# Alternative_bloinking_circuit_v0.net
KiCad netlist of a schematic drawn in EAGLE
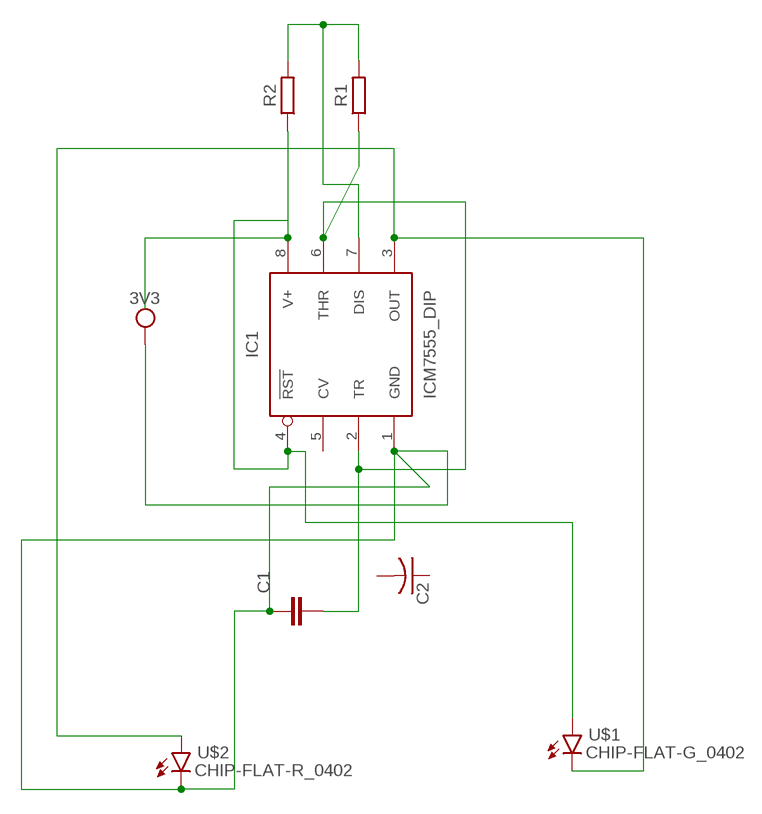
[diagram p0: schematic, sheet 1]

(export (version "E")
  (design (tool "Eeschema 10.0.6"))
  (components
    (comp (ref "C1")
      (value "C_CHIP-0402(1005-METRIC)")
      (footprint "eagle-import:CAPC1005X60")
      (libsource (lib "eagle-import") (part "CCHIP-0402(1005-METRIC)_"))
    )
    (comp (ref "C2")
      (value "C-US_CHIP-0402(1005-METRIC)")
      (footprint "eagle-import:CAPC1005X60")
      (libsource (lib "eagle-import") (part "C-USCHIP-0402(1005-METRIC)_"))
    )
    (comp (ref "IC1")
      (value "ICM7555_DIP")
      (footprint "eagle-import:DIP826W53P254L959H508Q8B")
      (fields
        (field (name "MANUFACTURER") "Renesas Electronics America Inc ")
        (field (name "MPN") "ICM7555IPAZ ")
      )
      (libsource (lib "eagle-import") (part "555_DIPICM7"))
    )
    (comp (ref "R1")
      (value "R_AXIAL-11.7MM-PITCH")
      (footprint "eagle-import:RESAD1176W63L850D250B")
      (libsource (lib "eagle-import") (part "RAXIAL-11.7MM-PITCH_"))
    )
    (comp (ref "R2")
      (value "R_AXIAL-7.2MM-PITCH")
      (footprint "eagle-import:RESAD724W46L381D178B")
      (libsource (lib "eagle-import") (part "RAXIAL-7.2MM-PITCH_"))
    )
    (comp (ref "U$1")
      (value "CHIP-FLAT-G_0402")
      (footprint "eagle-import:LEDC1005X25N")
      (libsource (lib "eagle-import") (part "CHIP-FLAT-G_0402"))
    )
    (comp (ref "U$2")
      (value "CHIP-FLAT-R_0402")
      (footprint "eagle-import:LEDC1005X25N")
      (libsource (lib "eagle-import") (part "CHIP-FLAT-R_0402"))
    )
  )
  (nets
    (net (code "1") (name "3V3") (class "Default")
      (node (ref "C1") (pin "1") (pinfunction "1_1") (pintype "passive"))
      (node (ref "IC1") (pin "1") (pinfunction "GND_1") (pintype "power_in"))
      (node (ref "U$2") (pin "C") (pinfunction "C_C") (pintype "passive"))
    )
    (net (code "2") (name "Net-(IC1-DIS)") (class "Default")
      (node (ref "IC1") (pin "7") (pinfunction "DIS_7") (pintype "input"))
      (node (ref "R1") (pin "2") (pinfunction "2_2") (pintype "passive"))
      (node (ref "R2") (pin "2") (pinfunction "2_2") (pintype "passive"))
    )
    (net (code "3") (name "Net-(IC1-OUT)") (class "Default")
      (node (ref "IC1") (pin "3") (pinfunction "OUT_3") (pintype "output"))
      (node (ref "U$1") (pin "C") (pinfunction "C_C") (pintype "passive"))
      (node (ref "U$2") (pin "A") (pinfunction "A_A") (pintype "passive"))
    )
    (net (code "4") (name "Net-(IC1-THR)") (class "Default")
      (node (ref "C1") (pin "2") (pinfunction "2_2") (pintype "passive"))
      (node (ref "IC1") (pin "2") (pinfunction "TR_2") (pintype "input"))
      (node (ref "IC1") (pin "6") (pinfunction "THR_6") (pintype "input"))
      (node (ref "R1") (pin "1") (pinfunction "1_1") (pintype "passive"))
    )
    (net (code "5") (name "Net-(IC1-V+)") (class "Default")
      (node (ref "IC1") (pin "4") (pinfunction "~{RST}_4") (pintype "input"))
      (node (ref "IC1") (pin "8") (pinfunction "V+_8") (pintype "power_in"))
      (node (ref "R2") (pin "1") (pinfunction "1_1") (pintype "passive"))
      (node (ref "U$1") (pin "A") (pinfunction "A_A") (pintype "passive"))
    )
    (net (code "6") (name "unconnected-(C2-Pad1)") (class "Default")
      (node (ref "C2") (pin "1") (pinfunction "1_1") (pintype "passive"))
    )
    (net (code "7") (name "unconnected-(C2-Pad2)") (class "Default")
      (node (ref "C2") (pin "2") (pinfunction "2_2") (pintype "passive"))
    )
    (net (code "8") (name "unconnected-(IC1-CV-Pad5)") (class "Default")
      (node (ref "IC1") (pin "5") (pinfunction "CV_5") (pintype "input"))
    )
  )
)
